# drum.net
KiCad netlist of a schematic drawn in EAGLE
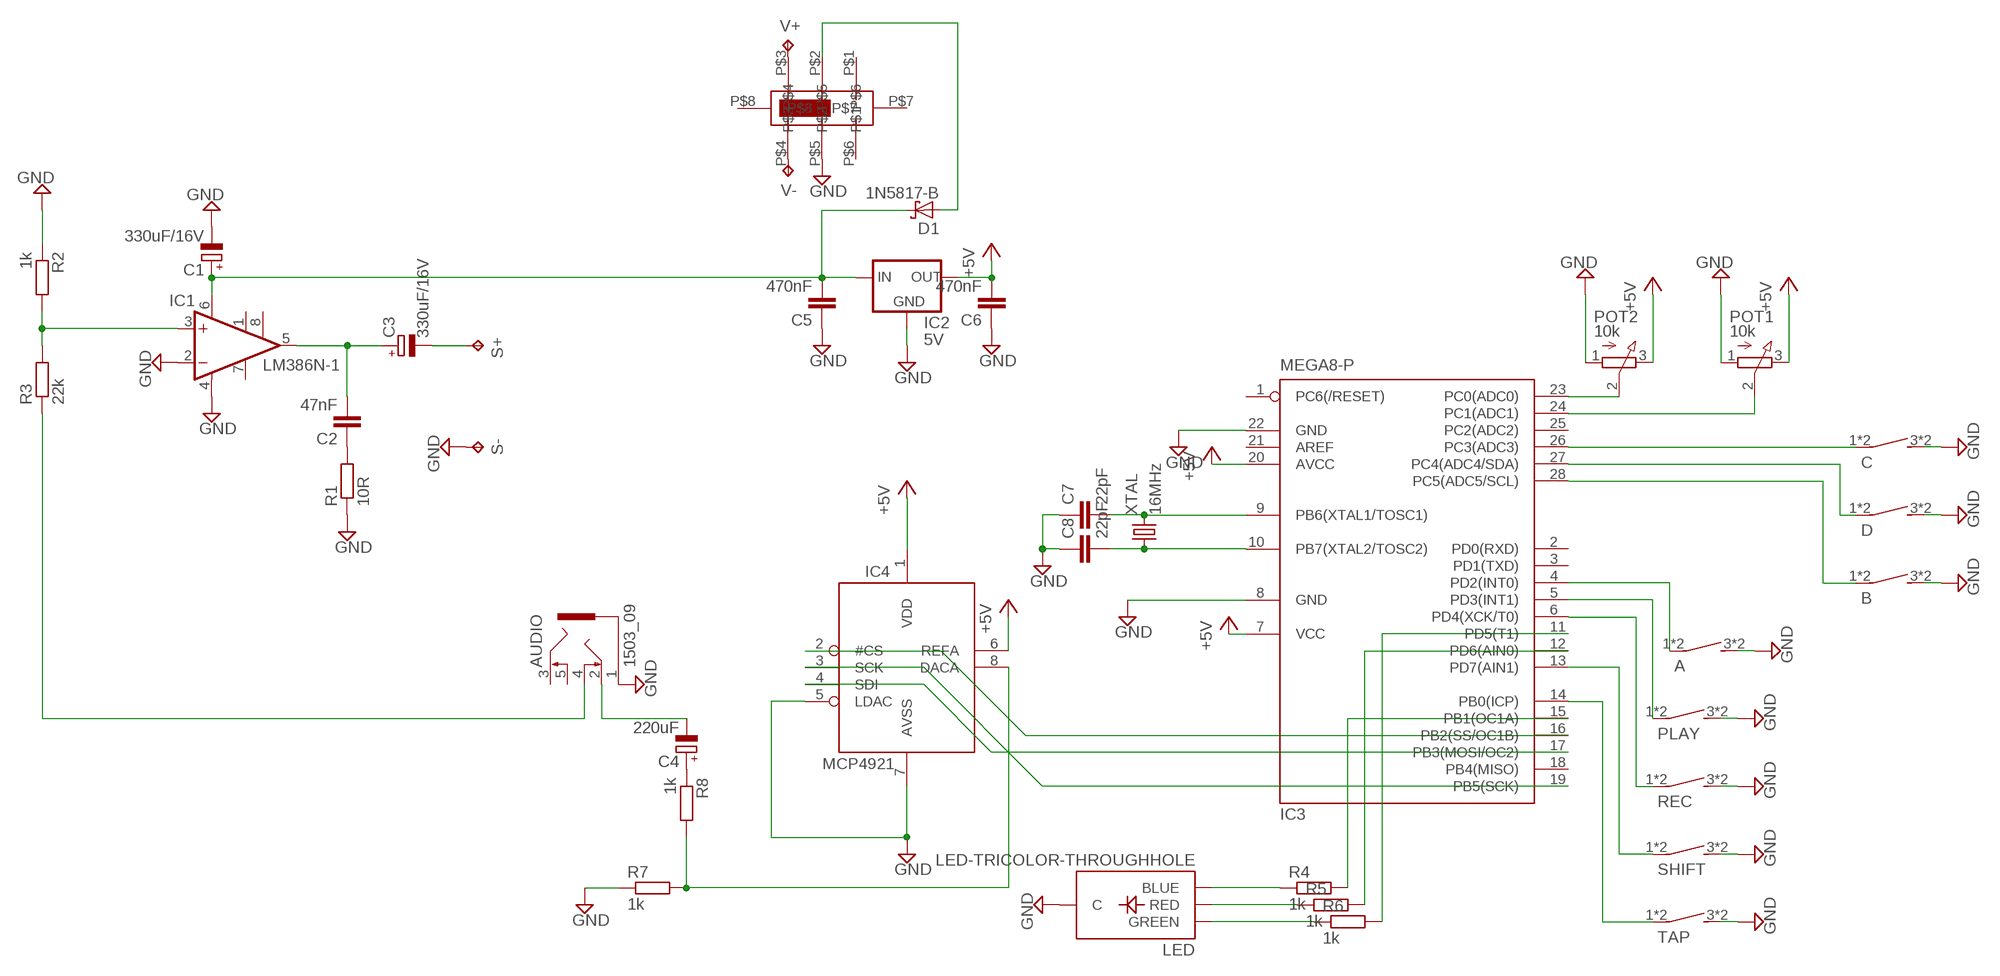
[diagram p0: schematic, sheet 1]

(export (version "E")
  (design (tool "Eeschema 10.0.6"))
  (components
    (comp (ref "A")
      (value "D6R_SPSTB3F-4000")
      (footprint "eagle-import:B3F-4000")
      (libsource (lib "eagle-import") (part "D6R_SPSTB3F-4000"))
    )
    (comp (ref "AUDIO")
      (value "1503_09")
      (footprint "eagle-import:1503_09")
      (libsource (lib "eagle-import") (part "1503_09"))
    )
    (comp (ref "B")
      (value "D6R_SPSTB3F-4000")
      (footprint "eagle-import:B3F-4000")
      (libsource (lib "eagle-import") (part "D6R_SPSTB3F-4000"))
    )
    (comp (ref "C")
      (value "D6R_SPSTB3F-4000")
      (footprint "eagle-import:B3F-4000")
      (libsource (lib "eagle-import") (part "D6R_SPSTB3F-4000"))
    )
    (comp (ref "C1")
      (value "330uF/16V")
      (footprint "eagle-import:E3,5-8")
      (libsource (lib "eagle-import") (part "CPOL-EUE3.5-8"))
    )
    (comp (ref "C2")
      (value "47nF")
      (footprint "eagle-import:C050-024X044")
      (libsource (lib "eagle-import") (part "C-EU050-024X044"))
    )
    (comp (ref "C3")
      (value "330uF/16V")
      (footprint "eagle-import:E3,5-8")
      (libsource (lib "eagle-import") (part "CPOL-EUE3.5-8"))
    )
    (comp (ref "C4")
      (value "220uF")
      (footprint "eagle-import:E2,5-6")
      (libsource (lib "eagle-import") (part "CPOL-EUE2.5-6"))
    )
    (comp (ref "C5")
      (value "470nF")
      (footprint "eagle-import:C050-024X044")
      (libsource (lib "eagle-import") (part "C-EU050-024X044"))
    )
    (comp (ref "C6")
      (value "470nF")
      (footprint "eagle-import:C050-024X044")
      (libsource (lib "eagle-import") (part "C-EU050-024X044"))
    )
    (comp (ref "C7")
      (value "22pF")
      (footprint "eagle-import:C050-024X044")
      (libsource (lib "eagle-import") (part "C-EU050-024X044"))
    )
    (comp (ref "C8")
      (value "22pF")
      (footprint "eagle-import:C050-024X044")
      (libsource (lib "eagle-import") (part "C-EU050-024X044"))
    )
    (comp (ref "D")
      (value "D6R_SPSTB3F-4000")
      (footprint "eagle-import:B3F-4000")
      (libsource (lib "eagle-import") (part "D6R_SPSTB3F-4000"))
    )
    (comp (ref "D1")
      (value "1N5817-B")
      (footprint "eagle-import:DO41-7.6")
      (libsource (lib "eagle-import") (part "1N5817-B"))
    )
    (comp (ref "IC1")
      (value "LM386N-1")
      (footprint "eagle-import:DIL08")
      (libsource (lib "eagle-import") (part "LM386?-N1"))
    )
    (comp (ref "IC2")
      (value "5V")
      (footprint "eagle-import:78LXX")
      (libsource (lib "eagle-import") (part "78LXX"))
    )
    (comp (ref "IC3")
      (value "MEGA8-P")
      (footprint "eagle-import:DIL28-3")
      (libsource (lib "eagle-import") (part "MEGA8-P"))
    )
    (comp (ref "IC4")
      (value "MCP4921")
      (footprint "eagle-import:DIL08")
      (libsource (lib "eagle-import") (part "MCP4921"))
    )
    (comp (ref "LED")
      (value "LED-TRICOLOR-THROUGHHOLE")
      (footprint "eagle-import:LED-TRICOLOR-THROUGHHOLE")
      (libsource (lib "eagle-import") (part "LED-TRICOLOR-THROUGHHOLE"))
    )
    (comp (ref "PLAY")
      (value "D6R_SPSTB3F-4000")
      (footprint "eagle-import:B3F-4000")
      (libsource (lib "eagle-import") (part "D6R_SPSTB3F-4000"))
    )
    (comp (ref "POT1")
      (value "10k")
      (footprint "eagle-import:EVUFXJ")
      (libsource (lib "eagle-import") (part "RK09K11310KBF2J"))
    )
    (comp (ref "POT2")
      (value "10k")
      (footprint "eagle-import:EVUFXJ")
      (libsource (lib "eagle-import") (part "RK09K11310KBF2J"))
    )
    (comp (ref "PWR")
      (value "SLIDE_SW_DPDT")
      (footprint "eagle-import:SS008B02P22")
      (libsource (lib "eagle-import") (part "SLIDE_SW_DPDT"))
    )
    (comp (ref "R1")
      (value "10R")
      (footprint "eagle-import:0207_10")
      (libsource (lib "eagle-import") (part "R-EU_0207/10"))
    )
    (comp (ref "R2")
      (value "1k")
      (footprint "eagle-import:0207_10")
      (libsource (lib "eagle-import") (part "R-EU_0207/10"))
    )
    (comp (ref "R3")
      (value "22k")
      (footprint "eagle-import:0207_10")
      (libsource (lib "eagle-import") (part "R-EU_0207/10"))
    )
    (comp (ref "R4")
      (value "1k")
      (footprint "eagle-import:0207_10")
      (libsource (lib "eagle-import") (part "R-EU_0207/10"))
    )
    (comp (ref "R5")
      (value "1k")
      (footprint "eagle-import:0207_10")
      (libsource (lib "eagle-import") (part "R-EU_0207/10"))
    )
    (comp (ref "R6")
      (value "1k")
      (footprint "eagle-import:0207_10")
      (libsource (lib "eagle-import") (part "R-EU_0207/10"))
    )
    (comp (ref "R7")
      (value "1k")
      (footprint "eagle-import:0207_10")
      (libsource (lib "eagle-import") (part "R-EU_0207/10"))
    )
    (comp (ref "R8")
      (value "1k")
      (footprint "eagle-import:0207_10")
      (libsource (lib "eagle-import") (part "R-EU_0207/10"))
    )
    (comp (ref "REC")
      (value "D6R_SPSTB3F-4000")
      (footprint "eagle-import:B3F-4000")
      (libsource (lib "eagle-import") (part "D6R_SPSTB3F-4000"))
    )
    (comp (ref "S+")
      (value "TPPAD1-17")
      (footprint "eagle-import:P1-17")
      (libsource (lib "eagle-import") (part "TPPAD1-17"))
    )
    (comp (ref "S-")
      (value "TPPAD1-17")
      (footprint "eagle-import:P1-17")
      (libsource (lib "eagle-import") (part "TPPAD1-17"))
    )
    (comp (ref "SHIFT")
      (value "D6R_SPSTB3F-4000")
      (footprint "eagle-import:B3F-4000")
      (libsource (lib "eagle-import") (part "D6R_SPSTB3F-4000"))
    )
    (comp (ref "TAP")
      (value "D6R_SPSTB3F-4000")
      (footprint "eagle-import:B3F-4000")
      (libsource (lib "eagle-import") (part "D6R_SPSTB3F-4000"))
    )
    (comp (ref "V+")
      (value "TPPAD1-17")
      (footprint "eagle-import:P1-17")
      (libsource (lib "eagle-import") (part "TPPAD1-17"))
    )
    (comp (ref "V-")
      (value "TPPAD1-17")
      (footprint "eagle-import:P1-17")
      (libsource (lib "eagle-import") (part "TPPAD1-17"))
    )
    (comp (ref "XTAL")
      (value "16MHz")
      (footprint "eagle-import:HC49_S")
      (libsource (lib "eagle-import") (part "CRYSTALHC49S"))
    )
  )
  (nets
    (net (code "1") (name "+5V") (class "Default")
      (node (ref "C6") (pin "2") (pinfunction "2_2") (pintype "passive"))
      (node (ref "IC2") (pin "OUT") (pinfunction "OUT_OUT") (pintype "passive"))
      (node (ref "IC3") (pin "20") (pinfunction "AVCC_20") (pintype "power_in"))
      (node (ref "IC3") (pin "7") (pinfunction "VCC_7") (pintype "power_in"))
      (node (ref "IC4") (pin "1") (pinfunction "VDD_1") (pintype "power_in"))
      (node (ref "IC4") (pin "6") (pinfunction "REFA_6") (pintype "input"))
      (node (ref "POT1") (pin "3") (pinfunction "E_3") (pintype "passive"))
      (node (ref "POT2") (pin "3") (pinfunction "E_3") (pintype "passive"))
    )
    (net (code "2") (name "GND") (class "Default")
      (node (ref "A") (pin "3") (pinfunction "S_3") (pintype "passive"))
      (node (ref "A") (pin "4") (pinfunction "S_4") (pintype "passive"))
      (node (ref "AUDIO") (pin "1") (pinfunction "1_1") (pintype "passive"))
      (node (ref "B") (pin "3") (pinfunction "S_3") (pintype "passive"))
      (node (ref "B") (pin "4") (pinfunction "S_4") (pintype "passive"))
      (node (ref "C") (pin "3") (pinfunction "S_3") (pintype "passive"))
      (node (ref "C") (pin "4") (pinfunction "S_4") (pintype "passive"))
      (node (ref "C1") (pin "-") (pinfunction "-_-") (pintype "passive"))
      (node (ref "C5") (pin "1") (pinfunction "1_1") (pintype "passive"))
      (node (ref "C6") (pin "1") (pinfunction "1_1") (pintype "passive"))
      (node (ref "C7") (pin "1") (pinfunction "1_1") (pintype "passive"))
      (node (ref "C8") (pin "1") (pinfunction "1_1") (pintype "passive"))
      (node (ref "D") (pin "3") (pinfunction "S_3") (pintype "passive"))
      (node (ref "D") (pin "4") (pinfunction "S_4") (pintype "passive"))
      (node (ref "IC1") (pin "2") (pinfunction "-IN_2") (pintype "input"))
      (node (ref "IC1") (pin "4") (pinfunction "GND_4") (pintype "power_in"))
      (node (ref "IC2") (pin "GND") (pinfunction "GND_GND") (pintype "input"))
      (node (ref "IC3") (pin "22") (pinfunction "GND_22") (pintype "power_in"))
      (node (ref "IC3") (pin "8") (pinfunction "GND_8") (pintype "power_in"))
      (node (ref "IC4") (pin "5") (pinfunction "LDAC_5") (pintype "input"))
      (node (ref "IC4") (pin "7") (pinfunction "AVSS_7") (pintype "power_in"))
      (node (ref "LED") (pin "GND") (pinfunction "C_GND") (pintype "bidirectional"))
      (node (ref "PLAY") (pin "3") (pinfunction "S_3") (pintype "passive"))
      (node (ref "PLAY") (pin "4") (pinfunction "S_4") (pintype "passive"))
      (node (ref "POT1") (pin "1") (pinfunction "A_1") (pintype "passive"))
      (node (ref "POT2") (pin "1") (pinfunction "A_1") (pintype "passive"))
      (node (ref "PWR") (pin "P$5") (pinfunction "P$5_P$5") (pintype "bidirectional"))
      (node (ref "R1") (pin "1") (pinfunction "1_1") (pintype "passive"))
      (node (ref "R2") (pin "1") (pinfunction "1_1") (pintype "passive"))
      (node (ref "R7") (pin "1") (pinfunction "1_1") (pintype "passive"))
      (node (ref "REC") (pin "3") (pinfunction "S_3") (pintype "passive"))
      (node (ref "REC") (pin "4") (pinfunction "S_4") (pintype "passive"))
      (node (ref "S-") (pin "TP") (pinfunction "TP_TP") (pintype "input"))
      (node (ref "SHIFT") (pin "3") (pinfunction "S_3") (pintype "passive"))
      (node (ref "SHIFT") (pin "4") (pinfunction "S_4") (pintype "passive"))
      (node (ref "TAP") (pin "3") (pinfunction "S_3") (pintype "passive"))
      (node (ref "TAP") (pin "4") (pinfunction "S_4") (pintype "passive"))
    )
    (net (code "3") (name "Net-(AUDIO-Pad2)") (class "Default")
      (node (ref "AUDIO") (pin "2") (pinfunction "2_2") (pintype "passive"))
      (node (ref "C4") (pin "-") (pinfunction "-_-") (pintype "passive"))
    )
    (net (code "4") (name "Net-(AUDIO-Pad4)") (class "Default")
      (node (ref "AUDIO") (pin "4") (pinfunction "4_4") (pintype "passive"))
      (node (ref "R3") (pin "1") (pinfunction "1_1") (pintype "passive"))
    )
    (net (code "5") (name "Net-(C2-Pad1)") (class "Default")
      (node (ref "C2") (pin "1") (pinfunction "1_1") (pintype "passive"))
      (node (ref "R1") (pin "2") (pinfunction "2_2") (pintype "passive"))
    )
    (net (code "6") (name "Net-(C3-Pad-)") (class "Default")
      (node (ref "C3") (pin "-") (pinfunction "-_-") (pintype "passive"))
      (node (ref "S+") (pin "TP") (pinfunction "TP_TP") (pintype "input"))
    )
    (net (code "7") (name "Net-(C4-Pad+)") (class "Default")
      (node (ref "C4") (pin "+") (pinfunction "+_+") (pintype "passive"))
      (node (ref "R8") (pin "1") (pinfunction "1_1") (pintype "passive"))
    )
    (net (code "8") (name "Net-(D1-PadA)") (class "Default")
      (node (ref "D1") (pin "A") (pinfunction "A_A") (pintype "passive"))
      (node (ref "PWR") (pin "P$2") (pinfunction "P$2_P$2") (pintype "bidirectional"))
    )
    (net (code "9") (name "Net-(IC1-+IN)") (class "Default")
      (node (ref "IC1") (pin "3") (pinfunction "+IN_3") (pintype "input"))
      (node (ref "R2") (pin "2") (pinfunction "2_2") (pintype "passive"))
      (node (ref "R3") (pin "2") (pinfunction "2_2") (pintype "passive"))
    )
    (net (code "10") (name "Net-(IC1-OUT)") (class "Default")
      (node (ref "C2") (pin "2") (pinfunction "2_2") (pintype "passive"))
      (node (ref "C3") (pin "+") (pinfunction "+_+") (pintype "passive"))
      (node (ref "IC1") (pin "5") (pinfunction "OUT_5") (pintype "output"))
    )
    (net (code "11") (name "Net-(IC1-VS)") (class "Default")
      (node (ref "C1") (pin "+") (pinfunction "+_+") (pintype "passive"))
      (node (ref "C5") (pin "2") (pinfunction "2_2") (pintype "passive"))
      (node (ref "D1") (pin "C") (pinfunction "C_C") (pintype "passive"))
      (node (ref "IC1") (pin "6") (pinfunction "VS_6") (pintype "power_in"))
      (node (ref "IC2") (pin "IN") (pinfunction "IN_IN") (pintype "input"))
    )
    (net (code "12") (name "Net-(IC3-PB0(ICP))") (class "Default")
      (node (ref "IC3") (pin "14") (pinfunction "PB0(ICP)_14") (pintype "bidirectional"))
      (node (ref "TAP") (pin "1") (pinfunction "P_1") (pintype "passive"))
      (node (ref "TAP") (pin "2") (pinfunction "P_2") (pintype "passive"))
    )
    (net (code "13") (name "Net-(IC3-PB1(OC1A))") (class "Default")
      (node (ref "IC3") (pin "15") (pinfunction "PB1(OC1A)_15") (pintype "bidirectional"))
      (node (ref "R4") (pin "2") (pinfunction "2_2") (pintype "passive"))
    )
    (net (code "14") (name "Net-(IC3-PB2(SS{slash}OC1B))") (class "Default")
      (node (ref "IC3") (pin "16") (pinfunction "PB2(SS/OC1B)_16") (pintype "bidirectional"))
      (node (ref "IC4") (pin "2") (pinfunction "#CS_2") (pintype "input"))
    )
    (net (code "15") (name "Net-(IC3-PB3(MOSI{slash}OC2))") (class "Default")
      (node (ref "IC3") (pin "17") (pinfunction "PB3(MOSI/OC2)_17") (pintype "bidirectional"))
      (node (ref "IC4") (pin "4") (pinfunction "SDI_4") (pintype "input"))
    )
    (net (code "16") (name "Net-(IC3-PB5(SCK))") (class "Default")
      (node (ref "IC3") (pin "19") (pinfunction "PB5(SCK)_19") (pintype "bidirectional"))
      (node (ref "IC4") (pin "3") (pinfunction "SCK_3") (pintype "input"))
    )
    (net (code "17") (name "Net-(IC3-PB6(XTAL1{slash}TOSC1))") (class "Default")
      (node (ref "C7") (pin "2") (pinfunction "2_2") (pintype "passive"))
      (node (ref "IC3") (pin "9") (pinfunction "PB6(XTAL1/TOSC1)_9") (pintype "bidirectional"))
      (node (ref "XTAL") (pin "2") (pinfunction "2_2") (pintype "passive"))
    )
    (net (code "18") (name "Net-(IC3-PB7(XTAL2{slash}TOSC2))") (class "Default")
      (node (ref "C8") (pin "2") (pinfunction "2_2") (pintype "passive"))
      (node (ref "IC3") (pin "10") (pinfunction "PB7(XTAL2/TOSC2)_10") (pintype "bidirectional"))
      (node (ref "XTAL") (pin "1") (pinfunction "1_1") (pintype "passive"))
    )
    (net (code "19") (name "Net-(IC3-PC0(ADC0))") (class "Default")
      (node (ref "IC3") (pin "23") (pinfunction "PC0(ADC0)_23") (pintype "bidirectional"))
      (node (ref "POT2") (pin "2") (pinfunction "S_2") (pintype "passive"))
    )
    (net (code "20") (name "Net-(IC3-PC1(ADC1))") (class "Default")
      (node (ref "IC3") (pin "24") (pinfunction "PC1(ADC1)_24") (pintype "bidirectional"))
      (node (ref "POT1") (pin "2") (pinfunction "S_2") (pintype "passive"))
    )
    (net (code "21") (name "Net-(IC3-PC3(ADC3))") (class "Default")
      (node (ref "C") (pin "1") (pinfunction "P_1") (pintype "passive"))
      (node (ref "C") (pin "2") (pinfunction "P_2") (pintype "passive"))
      (node (ref "IC3") (pin "26") (pinfunction "PC3(ADC3)_26") (pintype "bidirectional"))
    )
    (net (code "22") (name "Net-(IC3-PC4(ADC4{slash}SDA))") (class "Default")
      (node (ref "D") (pin "1") (pinfunction "P_1") (pintype "passive"))
      (node (ref "D") (pin "2") (pinfunction "P_2") (pintype "passive"))
      (node (ref "IC3") (pin "27") (pinfunction "PC4(ADC4/SDA)_27") (pintype "bidirectional"))
    )
    (net (code "23") (name "Net-(IC3-PC5(ADC5{slash}SCL))") (class "Default")
      (node (ref "B") (pin "1") (pinfunction "P_1") (pintype "passive"))
      (node (ref "B") (pin "2") (pinfunction "P_2") (pintype "passive"))
      (node (ref "IC3") (pin "28") (pinfunction "PC5(ADC5/SCL)_28") (pintype "bidirectional"))
    )
    (net (code "24") (name "Net-(IC3-PD2(INT0))") (class "Default")
      (node (ref "A") (pin "1") (pinfunction "P_1") (pintype "passive"))
      (node (ref "A") (pin "2") (pinfunction "P_2") (pintype "passive"))
      (node (ref "IC3") (pin "4") (pinfunction "PD2(INT0)_4") (pintype "bidirectional"))
    )
    (net (code "25") (name "Net-(IC3-PD3(INT1))") (class "Default")
      (node (ref "IC3") (pin "5") (pinfunction "PD3(INT1)_5") (pintype "bidirectional"))
      (node (ref "PLAY") (pin "1") (pinfunction "P_1") (pintype "passive"))
      (node (ref "PLAY") (pin "2") (pinfunction "P_2") (pintype "passive"))
    )
    (net (code "26") (name "Net-(IC3-PD4(XCK{slash}T0))") (class "Default")
      (node (ref "IC3") (pin "6") (pinfunction "PD4(XCK/T0)_6") (pintype "bidirectional"))
      (node (ref "REC") (pin "1") (pinfunction "P_1") (pintype "passive"))
      (node (ref "REC") (pin "2") (pinfunction "P_2") (pintype "passive"))
    )
    (net (code "27") (name "Net-(IC3-PD5(T1))") (class "Default")
      (node (ref "IC3") (pin "11") (pinfunction "PD5(T1)_11") (pintype "bidirectional"))
      (node (ref "R6") (pin "2") (pinfunction "2_2") (pintype "passive"))
    )
    (net (code "28") (name "Net-(IC3-PD6(AIN0))") (class "Default")
      (node (ref "IC3") (pin "12") (pinfunction "PD6(AIN0)_12") (pintype "bidirectional"))
      (node (ref "R5") (pin "2") (pinfunction "2_2") (pintype "passive"))
    )
    (net (code "29") (name "Net-(IC3-PD7(AIN1))") (class "Default")
      (node (ref "IC3") (pin "13") (pinfunction "PD7(AIN1)_13") (pintype "bidirectional"))
      (node (ref "SHIFT") (pin "1") (pinfunction "P_1") (pintype "passive"))
      (node (ref "SHIFT") (pin "2") (pinfunction "P_2") (pintype "passive"))
    )
    (net (code "30") (name "Net-(IC4-DACA)") (class "Default")
      (node (ref "IC4") (pin "8") (pinfunction "DACA_8") (pintype "output"))
      (node (ref "R7") (pin "2") (pinfunction "2_2") (pintype "passive"))
      (node (ref "R8") (pin "2") (pinfunction "2_2") (pintype "passive"))
    )
    (net (code "31") (name "Net-(LED-BLUE)") (class "Default")
      (node (ref "LED") (pin "GRN") (pinfunction "BLUE_GRN") (pintype "bidirectional"))
      (node (ref "R4") (pin "1") (pinfunction "1_1") (pintype "passive"))
    )
    (net (code "32") (name "Net-(LED-GREEN)") (class "Default")
      (node (ref "LED") (pin "RED") (pinfunction "GREEN_RED") (pintype "bidirectional"))
      (node (ref "R6") (pin "1") (pinfunction "1_1") (pintype "passive"))
    )
    (net (code "33") (name "Net-(LED-RED)") (class "Default")
      (node (ref "LED") (pin "BLU") (pinfunction "RED_BLU") (pintype "bidirectional"))
      (node (ref "R5") (pin "1") (pinfunction "1_1") (pintype "passive"))
    )
    (net (code "34") (name "Net-(PWR-PadP$3)") (class "Default")
      (node (ref "PWR") (pin "P$3") (pinfunction "P$3_P$3") (pintype "bidirectional"))
      (node (ref "V+") (pin "TP") (pinfunction "TP_TP") (pintype "input"))
    )
    (net (code "35") (name "Net-(PWR-PadP$4)") (class "Default")
      (node (ref "PWR") (pin "P$4") (pinfunction "P$4_P$4") (pintype "bidirectional"))
      (node (ref "V-") (pin "TP") (pinfunction "TP_TP") (pintype "input"))
    )
    (net (code "36") (name "unconnected-(AUDIO-Pad3)") (class "Default")
      (node (ref "AUDIO") (pin "3") (pinfunction "3_3") (pintype "passive"))
    )
    (net (code "37") (name "unconnected-(AUDIO-Pad5)") (class "Default")
      (node (ref "AUDIO") (pin "5") (pinfunction "5_5") (pintype "passive"))
    )
    (net (code "38") (name "unconnected-(IC1-BYPASS-Pad7)") (class "Default")
      (node (ref "IC1") (pin "7") (pinfunction "BYPASS_7") (pintype "passive"))
    )
    (net (code "39") (name "unconnected-(IC1-GAIN-Pad1)") (class "Default")
      (node (ref "IC1") (pin "1") (pinfunction "GAIN_1") (pintype "passive"))
    )
    (net (code "40") (name "unconnected-(IC1-GAIN-Pad8)") (class "Default")
      (node (ref "IC1") (pin "8") (pinfunction "GAIN_8") (pintype "passive"))
    )
    (net (code "41") (name "unconnected-(IC3-AREF-Pad21)") (class "Default")
      (node (ref "IC3") (pin "21") (pinfunction "AREF_21") (pintype "passive"))
    )
    (net (code "42") (name "unconnected-(IC3-PB4(MISO)-Pad18)") (class "Default")
      (node (ref "IC3") (pin "18") (pinfunction "PB4(MISO)_18") (pintype "bidirectional"))
    )
    (net (code "43") (name "unconnected-(IC3-PC2(ADC2)-Pad25)") (class "Default")
      (node (ref "IC3") (pin "25") (pinfunction "PC2(ADC2)_25") (pintype "bidirectional"))
    )
    (net (code "44") (name "unconnected-(IC3-PC6({slash}RESET)-Pad1)") (class "Default")
      (node (ref "IC3") (pin "1") (pinfunction "PC6(/RESET)_1") (pintype "bidirectional"))
    )
    (net (code "45") (name "unconnected-(IC3-PD0(RXD)-Pad2)") (class "Default")
      (node (ref "IC3") (pin "2") (pinfunction "PD0(RXD)_2") (pintype "bidirectional"))
    )
    (net (code "46") (name "unconnected-(IC3-PD1(TXD)-Pad3)") (class "Default")
      (node (ref "IC3") (pin "3") (pinfunction "PD1(TXD)_3") (pintype "bidirectional"))
    )
    (net (code "47") (name "unconnected-(PWR-PadP$1)") (class "Default")
      (node (ref "PWR") (pin "P$1") (pinfunction "P$1_P$1") (pintype "bidirectional"))
    )
    (net (code "48") (name "unconnected-(PWR-PadP$6)") (class "Default")
      (node (ref "PWR") (pin "P$6") (pinfunction "P$6_P$6") (pintype "bidirectional"))
    )
    (net (code "49") (name "unconnected-(PWR-PadP$7)") (class "Default")
      (node (ref "PWR") (pin "P$7") (pinfunction "P$7_P$7") (pintype "bidirectional"))
    )
    (net (code "50") (name "unconnected-(PWR-PadP$8)") (class "Default")
      (node (ref "PWR") (pin "P$8") (pinfunction "P$8_P$8") (pintype "bidirectional"))
    )
  )
)
